# left_revision3_0.net
KiCad netlist of a schematic drawn in EAGLE
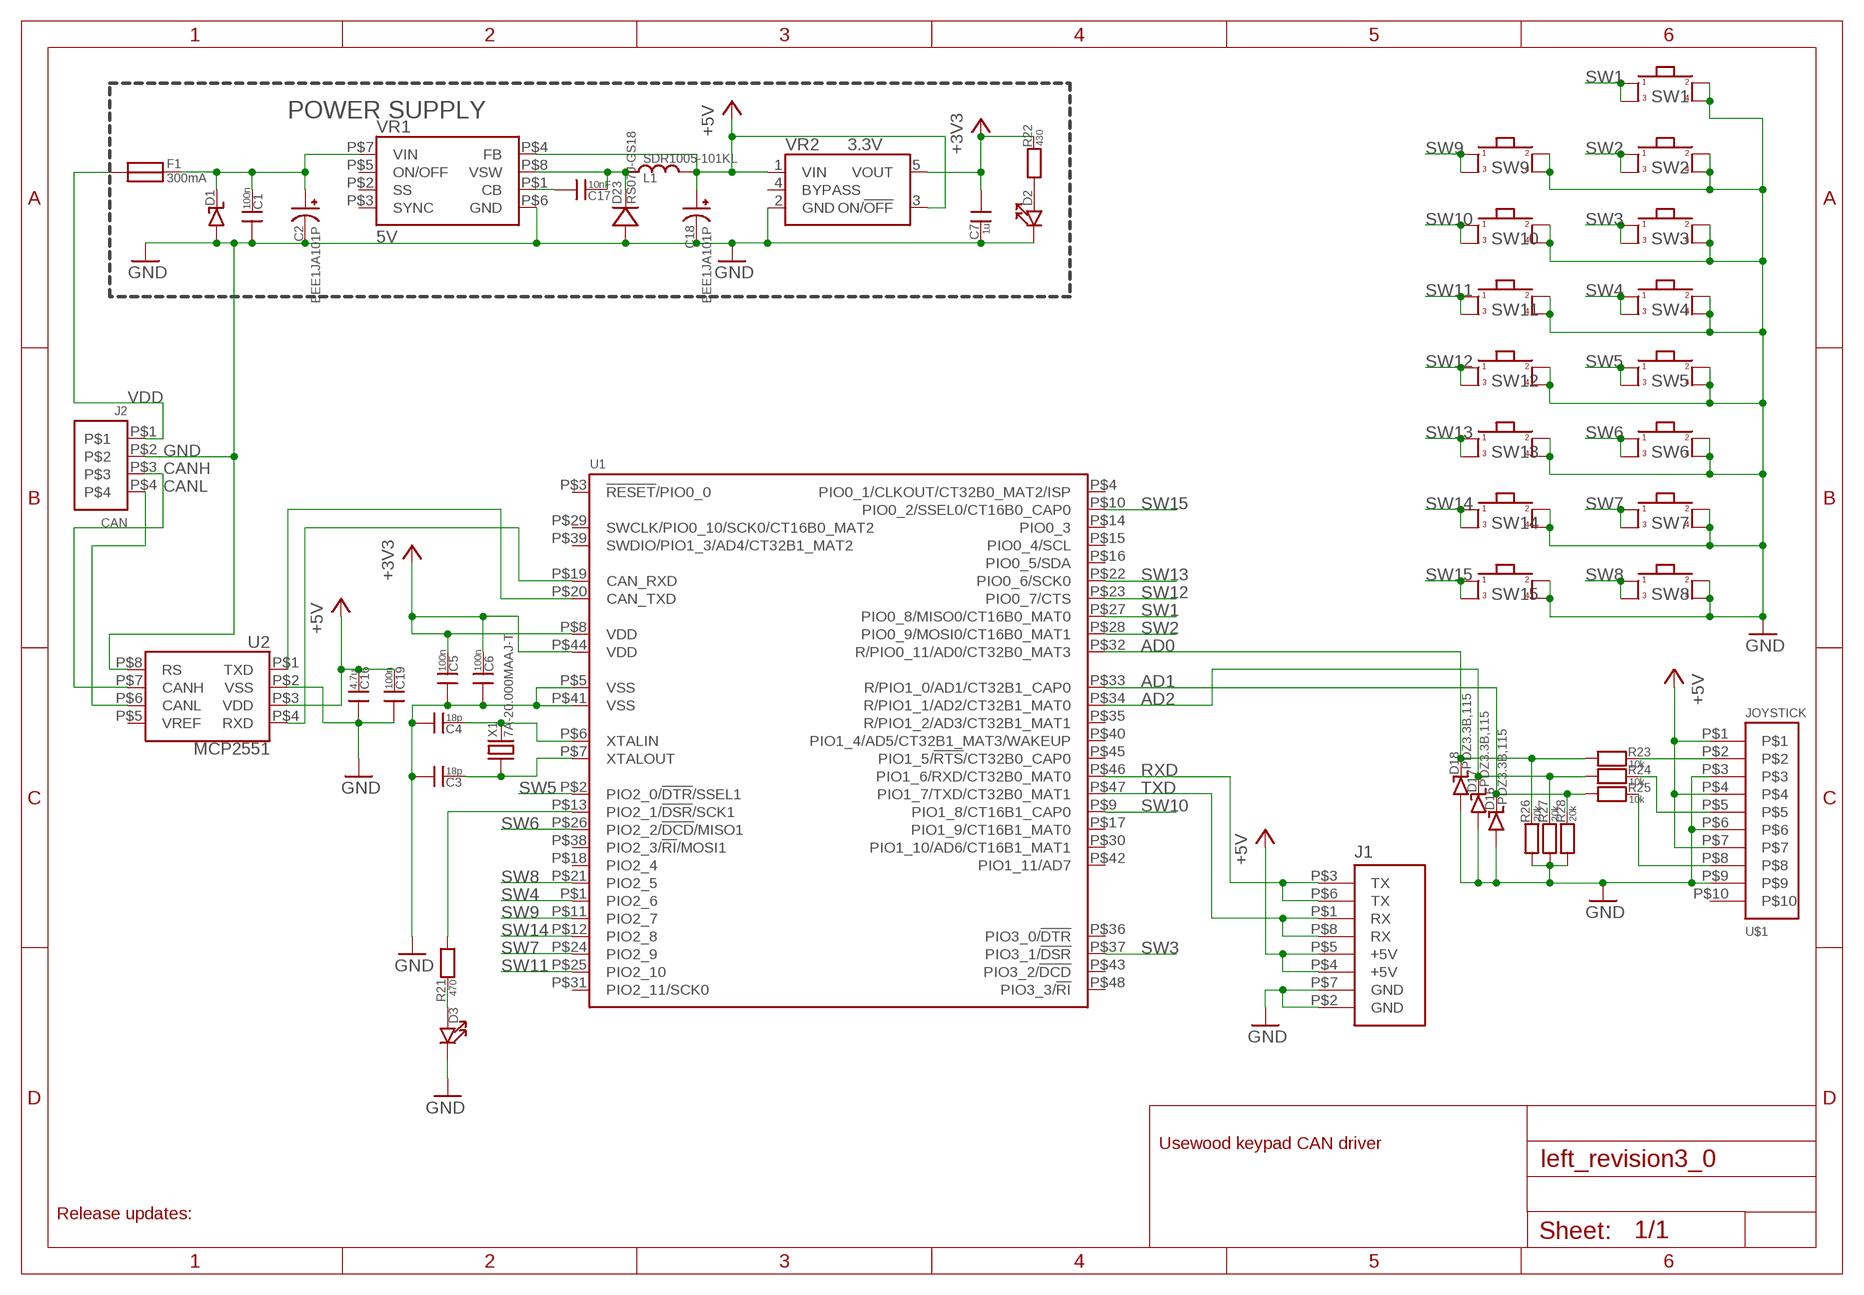
[diagram p0: schematic, sheet 1]

(export (version "E")
  (design (tool "Eeschema 10.0.6"))
  (components
    (comp (ref "C1")
      (value "100n")
      (footprint "eagle-import:0603_SILKSCREEN")
      (libsource (lib "eagle-import") (part "CAP_0603"))
    )
    (comp (ref "C2")
      (value "EEE1JA101P")
      (footprint "eagle-import:CAP_POL_SMD_10X10X10MM")
      (libsource (lib "eagle-import") (part "CAP_POLSMD_10X10X10MM"))
    )
    (comp (ref "C3")
      (value "18p")
      (footprint "eagle-import:0603_SILKSCREEN")
      (libsource (lib "eagle-import") (part "CAP_0603"))
    )
    (comp (ref "C4")
      (value "18p")
      (footprint "eagle-import:0603_SILKSCREEN")
      (libsource (lib "eagle-import") (part "CAP_0603"))
    )
    (comp (ref "C5")
      (value "100n")
      (footprint "eagle-import:0603_SILKSCREEN")
      (libsource (lib "eagle-import") (part "CAP_0603"))
    )
    (comp (ref "C6")
      (value "100n")
      (footprint "eagle-import:0603_SILKSCREEN")
      (libsource (lib "eagle-import") (part "CAP_0603"))
    )
    (comp (ref "C7")
      (value "1u")
      (footprint "eagle-import:0603_SILKSCREEN")
      (libsource (lib "eagle-import") (part "CAP_0603"))
    )
    (comp (ref "C16")
      (value "4.7u")
      (footprint "eagle-import:0603_SILKSCREEN")
      (libsource (lib "eagle-import") (part "CAP_0603"))
    )
    (comp (ref "C17")
      (value "10nF")
      (footprint "eagle-import:0603_SILKSCREEN")
      (libsource (lib "eagle-import") (part "CAP_0603"))
    )
    (comp (ref "C18")
      (value "EEE1JA101P")
      (footprint "eagle-import:CAP_POL_SMD_10X10X10MM")
      (libsource (lib "eagle-import") (part "CAP_POLSMD_10X10X10MM"))
    )
    (comp (ref "C19")
      (value "100n")
      (footprint "eagle-import:0603_SILKSCREEN")
      (libsource (lib "eagle-import") (part "CAP_0603"))
    )
    (comp (ref "D1")
      (value "DIODE_TVSDO-214AA")
      (footprint "eagle-import:DO-214AB")
      (libsource (lib "eagle-import") (part "DIODE_TVSDO-214AA"))
    )
    (comp (ref "D2")
      (value "LED_0603")
      (footprint "eagle-import:0603_SILKSCREEN")
      (libsource (lib "eagle-import") (part "LED_0603"))
    )
    (comp (ref "D3")
      (value "LED_0603")
      (footprint "eagle-import:0603_SILKSCREEN")
      (libsource (lib "eagle-import") (part "LED_0603"))
    )
    (comp (ref "D16")
      (value "PDZ3.3B,115")
      (footprint "eagle-import:SOD123")
      (libsource (lib "eagle-import") (part "DIODE_ZENERSDO123"))
    )
    (comp (ref "D17")
      (value "PDZ3.3B,115")
      (footprint "eagle-import:SOD123")
      (libsource (lib "eagle-import") (part "DIODE_ZENERSDO123"))
    )
    (comp (ref "D18")
      (value "PDZ3.3B,115")
      (footprint "eagle-import:SOD123")
      (libsource (lib "eagle-import") (part "DIODE_ZENERSDO123"))
    )
    (comp (ref "D23")
      (value "RS07J-GS18")
      (footprint "eagle-import:DO219AB")
      (libsource (lib "eagle-import") (part "DIODEDO219AB"))
    )
    (comp (ref "F1")
      (value "300mA")
      (footprint "eagle-import:FUSE_100MA")
      (libsource (lib "eagle-import") (part "FUSE_MC36204_100MA"))
    )
    (comp (ref "J1")
      (value "HEADER_USART_2_SMD")
      (footprint "eagle-import:HEADER_4_2_SMD")
      (libsource (lib "eagle-import") (part "HEADER_USART_2_SMD"))
    )
    (comp (ref "J2")
      (value "CAN")
      (footprint "eagle-import:MOLEX_MICRO_FIT_4WAY_SMD")
      (libsource (lib "eagle-import") (part "MOLEX_MICRO-FIT_4WAY_SMD"))
    )
    (comp (ref "L1")
      (value "SDR1005-101KL")
      (footprint "eagle-import:INDUCTOR_BOURNS_10X13X5MM")
      (libsource (lib "eagle-import") (part "INDUCTORBOURNS_10X13X5MM"))
    )
    (comp (ref "R21")
      (value "470")
      (footprint "eagle-import:0603_SILKSCREEN")
      (libsource (lib "eagle-import") (part "RES_0603"))
    )
    (comp (ref "R22")
      (value "430")
      (footprint "eagle-import:0603_SILKSCREEN")
      (libsource (lib "eagle-import") (part "RES_0603"))
    )
    (comp (ref "R23")
      (value "10k")
      (footprint "eagle-import:0603_SILKSCREEN")
      (libsource (lib "eagle-import") (part "RES_0603"))
    )
    (comp (ref "R24")
      (value "10k")
      (footprint "eagle-import:0603_SILKSCREEN")
      (libsource (lib "eagle-import") (part "RES_0603"))
    )
    (comp (ref "R25")
      (value "10k")
      (footprint "eagle-import:0603_SILKSCREEN")
      (libsource (lib "eagle-import") (part "RES_0603"))
    )
    (comp (ref "R26")
      (value "20k")
      (footprint "eagle-import:0603_SILKSCREEN")
      (libsource (lib "eagle-import") (part "RES_0603"))
    )
    (comp (ref "R27")
      (value "20k")
      (footprint "eagle-import:0603_SILKSCREEN")
      (libsource (lib "eagle-import") (part "RES_0603"))
    )
    (comp (ref "R28")
      (value "20k")
      (footprint "eagle-import:0603_SILKSCREEN")
      (libsource (lib "eagle-import") (part "RES_0603"))
    )
    (comp (ref "SW1")
      (value "SWITCH_EVQP6L")
      (footprint "eagle-import:SWITCH_EVQ9P6B40")
      (libsource (lib "eagle-import") (part "SWITCH_EVQP6L"))
    )
    (comp (ref "SW2")
      (value "SWITCH_EVQP6L")
      (footprint "eagle-import:SWITCH_EVQ9P6B40")
      (libsource (lib "eagle-import") (part "SWITCH_EVQP6L"))
    )
    (comp (ref "SW3")
      (value "SWITCH_EVQP6L")
      (footprint "eagle-import:SWITCH_EVQ9P6B40")
      (libsource (lib "eagle-import") (part "SWITCH_EVQP6L"))
    )
    (comp (ref "SW4")
      (value "SWITCH_EVQP6L")
      (footprint "eagle-import:SWITCH_EVQ9P6B40")
      (libsource (lib "eagle-import") (part "SWITCH_EVQP6L"))
    )
    (comp (ref "SW5")
      (value "SWITCH_EVQP6L")
      (footprint "eagle-import:SWITCH_EVQ9P6B40")
      (libsource (lib "eagle-import") (part "SWITCH_EVQP6L"))
    )
    (comp (ref "SW6")
      (value "SWITCH_EVQP6L")
      (footprint "eagle-import:SWITCH_EVQ9P6B40")
      (libsource (lib "eagle-import") (part "SWITCH_EVQP6L"))
    )
    (comp (ref "SW7")
      (value "SWITCH_EVQP6L")
      (footprint "eagle-import:SWITCH_EVQ9P6B40")
      (libsource (lib "eagle-import") (part "SWITCH_EVQP6L"))
    )
    (comp (ref "SW8")
      (value "SWITCH_EVQP6L")
      (footprint "eagle-import:SWITCH_EVQ9P6B40")
      (libsource (lib "eagle-import") (part "SWITCH_EVQP6L"))
    )
    (comp (ref "SW9")
      (value "SWITCH_EVQP6L")
      (footprint "eagle-import:SWITCH_EVQ9P6B40")
      (libsource (lib "eagle-import") (part "SWITCH_EVQP6L"))
    )
    (comp (ref "SW10")
      (value "SWITCH_EVQP6L")
      (footprint "eagle-import:SWITCH_EVQ9P6B40")
      (libsource (lib "eagle-import") (part "SWITCH_EVQP6L"))
    )
    (comp (ref "SW11")
      (value "SWITCH_EVQP6L")
      (footprint "eagle-import:SWITCH_EVQ9P6B40")
      (libsource (lib "eagle-import") (part "SWITCH_EVQP6L"))
    )
    (comp (ref "SW12")
      (value "SWITCH_EVQP6L")
      (footprint "eagle-import:SWITCH_EVQ9P6B40")
      (libsource (lib "eagle-import") (part "SWITCH_EVQP6L"))
    )
    (comp (ref "SW13")
      (value "SWITCH_EVQP6L")
      (footprint "eagle-import:SWITCH_EVQ9P6B40")
      (libsource (lib "eagle-import") (part "SWITCH_EVQP6L"))
    )
    (comp (ref "SW14")
      (value "SWITCH_EVQP6L")
      (footprint "eagle-import:SWITCH_EVQ9P6B40")
      (libsource (lib "eagle-import") (part "SWITCH_EVQP6L"))
    )
    (comp (ref "SW15")
      (value "SWITCH_EVQP6L")
      (footprint "eagle-import:SWITCH_EVQ9P6B40")
      (libsource (lib "eagle-import") (part "SWITCH_EVQP6L"))
    )
    (comp (ref "U$1")
      (value "JOYSTICK")
      (footprint "eagle-import:MOLEX_MICRO_FIT_10WAY_SMD")
      (libsource (lib "eagle-import") (part "MOLEX_MICRO-FIT_10WAY_SMD"))
    )
    (comp (ref "U1")
      (value "LPC11C14_QFP48")
      (footprint "eagle-import:QFP48")
      (libsource (lib "eagle-import") (part "LPC11C14_QFP48"))
    )
    (comp (ref "U2")
      (value "MCP2551")
      (footprint "eagle-import:SOIC8")
      (libsource (lib "eagle-import") (part "MCP2551_SOIC8"))
    )
    (comp (ref "VR1")
      (value "5V")
      (footprint "eagle-import:SOIC8")
      (libsource (lib "eagle-import") (part "LM2671SOIC8"))
    )
    (comp (ref "VR2")
      (value "3.3V")
      (footprint "eagle-import:SOP5")
      (libsource (lib "eagle-import") (part "REG_LP2985_SOP5"))
    )
    (comp (ref "X1")
      (value "7A-20.000MAAJ-T")
      (footprint "eagle-import:XTAL_SMD_5X3.2")
      (libsource (lib "eagle-import") (part "XTAL_7A-12.000MAAJ-T"))
    )
  )
  (nets
    (net (code "1") (name "+3V3") (class "Default")
      (node (ref "C5") (pin "1") (pinfunction "P$2_1") (pintype "bidirectional"))
      (node (ref "C6") (pin "1") (pinfunction "P$2_1") (pintype "bidirectional"))
      (node (ref "C7") (pin "0") (pinfunction "P$1_0") (pintype "bidirectional"))
      (node (ref "R22") (pin "1") (pinfunction "P$2_1") (pintype "bidirectional"))
      (node (ref "U1") (pin "P$44") (pinfunction "VDD_P$44") (pintype "bidirectional"))
      (node (ref "U1") (pin "P$8") (pinfunction "VDD_P$8") (pintype "bidirectional"))
      (node (ref "VR2") (pin "5") (pinfunction "VOUT_5") (pintype "bidirectional"))
    )
    (net (code "2") (name "+5V") (class "Default")
      (node (ref "C16") (pin "1") (pinfunction "P$2_1") (pintype "bidirectional"))
      (node (ref "C18") (pin "+") (pinfunction "+_+") (pintype "bidirectional"))
      (node (ref "C19") (pin "1") (pinfunction "P$2_1") (pintype "bidirectional"))
      (node (ref "J1") (pin "P$4") (pinfunction "+5V_P$4") (pintype "bidirectional"))
      (node (ref "J1") (pin "P$5") (pinfunction "+5V_P$5") (pintype "bidirectional"))
      (node (ref "L1") (pin "P$2") (pinfunction "P$2_P$2") (pintype "bidirectional"))
      (node (ref "U$1") (pin "P$1") (pinfunction "P$1_P$1") (pintype "bidirectional"))
      (node (ref "U$1") (pin "P$4") (pinfunction "P$4_P$4") (pintype "bidirectional"))
      (node (ref "U$1") (pin "P$7") (pinfunction "P$7_P$7") (pintype "bidirectional"))
      (node (ref "U2") (pin "P$3") (pinfunction "VDD_P$3") (pintype "bidirectional"))
      (node (ref "VR1") (pin "P$4") (pinfunction "FB_P$4") (pintype "bidirectional"))
      (node (ref "VR2") (pin "1") (pinfunction "VIN_1") (pintype "bidirectional"))
      (node (ref "VR2") (pin "3") (pinfunction "ON/~{OFF}_3") (pintype "bidirectional"))
    )
    (net (code "3") (name "/AD0") (class "Default")
      (node (ref "D18") (pin "P$2") (pinfunction "N_P$2") (pintype "bidirectional"))
      (node (ref "R23") (pin "0") (pinfunction "P$1_0") (pintype "bidirectional"))
      (node (ref "R26") (pin "1") (pinfunction "P$2_1") (pintype "bidirectional"))
      (node (ref "U1") (pin "P$32") (pinfunction "R/PIO0_11/AD0/CT32B0_MAT3_P$32") (pintype "bidirectional"))
    )
    (net (code "4") (name "/AD1") (class "Default")
      (node (ref "D16") (pin "P$2") (pinfunction "N_P$2") (pintype "bidirectional"))
      (node (ref "R25") (pin "0") (pinfunction "P$1_0") (pintype "bidirectional"))
      (node (ref "R28") (pin "1") (pinfunction "P$2_1") (pintype "bidirectional"))
      (node (ref "U1") (pin "P$33") (pinfunction "R/PIO1_0/AD1/CT32B1_CAP0_P$33") (pintype "bidirectional"))
    )
    (net (code "5") (name "/AD2") (class "Default")
      (node (ref "D17") (pin "P$2") (pinfunction "N_P$2") (pintype "bidirectional"))
      (node (ref "R24") (pin "0") (pinfunction "P$1_0") (pintype "bidirectional"))
      (node (ref "R27") (pin "1") (pinfunction "P$2_1") (pintype "bidirectional"))
      (node (ref "U1") (pin "P$34") (pinfunction "R/PIO1_1/AD2/CT32B1_MAT0_P$34") (pintype "bidirectional"))
    )
    (net (code "6") (name "/CANH") (class "Default")
      (node (ref "J2") (pin "P$3") (pinfunction "P$3_P$3") (pintype "bidirectional"))
      (node (ref "U2") (pin "P$7") (pinfunction "CANH_P$7") (pintype "bidirectional"))
    )
    (net (code "7") (name "/CANL") (class "Default")
      (node (ref "J2") (pin "P$4") (pinfunction "P$4_P$4") (pintype "bidirectional"))
      (node (ref "U2") (pin "P$6") (pinfunction "CANL_P$6") (pintype "bidirectional"))
    )
    (net (code "8") (name "/RXD") (class "Default")
      (node (ref "J1") (pin "P$3") (pinfunction "TX_P$3") (pintype "bidirectional"))
      (node (ref "J1") (pin "P$6") (pinfunction "TX_P$6") (pintype "bidirectional"))
      (node (ref "U1") (pin "P$46") (pinfunction "PIO1_6/RXD/CT32B0_MAT0_P$46") (pintype "bidirectional"))
    )
    (net (code "9") (name "/SW1") (class "Default")
      (node (ref "SW1") (pin "A") (pinfunction "P$1_A") (pintype "bidirectional"))
      (node (ref "SW1") (pin "A'") (pinfunction "P$3_A'") (pintype "bidirectional"))
      (node (ref "U1") (pin "P$27") (pinfunction "PIO0_8/MISO0/CT16B0_MAT0_P$27") (pintype "bidirectional"))
    )
    (net (code "10") (name "/SW2") (class "Default")
      (node (ref "SW2") (pin "A") (pinfunction "P$1_A") (pintype "bidirectional"))
      (node (ref "SW2") (pin "A'") (pinfunction "P$3_A'") (pintype "bidirectional"))
      (node (ref "U1") (pin "P$28") (pinfunction "PIO0_9/MOSI0/CT16B0_MAT1_P$28") (pintype "bidirectional"))
    )
    (net (code "11") (name "/SW3") (class "Default")
      (node (ref "SW3") (pin "A") (pinfunction "P$1_A") (pintype "bidirectional"))
      (node (ref "SW3") (pin "A'") (pinfunction "P$3_A'") (pintype "bidirectional"))
      (node (ref "U1") (pin "P$37") (pinfunction "PIO3_1/~{DSR}_P$37") (pintype "bidirectional"))
    )
    (net (code "12") (name "/SW4") (class "Default")
      (node (ref "SW4") (pin "A") (pinfunction "P$1_A") (pintype "bidirectional"))
      (node (ref "SW4") (pin "A'") (pinfunction "P$3_A'") (pintype "bidirectional"))
      (node (ref "U1") (pin "P$1") (pinfunction "PIO2_6_P$1") (pintype "bidirectional"))
    )
    (net (code "13") (name "/SW5") (class "Default")
      (node (ref "SW5") (pin "A") (pinfunction "P$1_A") (pintype "bidirectional"))
      (node (ref "SW5") (pin "A'") (pinfunction "P$3_A'") (pintype "bidirectional"))
      (node (ref "U1") (pin "P$2") (pinfunction "PIO2_0/~{DTR}/SSEL1_P$2") (pintype "bidirectional"))
    )
    (net (code "14") (name "/SW6") (class "Default")
      (node (ref "SW6") (pin "A") (pinfunction "P$1_A") (pintype "bidirectional"))
      (node (ref "SW6") (pin "A'") (pinfunction "P$3_A'") (pintype "bidirectional"))
      (node (ref "U1") (pin "P$26") (pinfunction "PIO2_2/~{DCD}/MISO1_P$26") (pintype "bidirectional"))
    )
    (net (code "15") (name "/SW7") (class "Default")
      (node (ref "SW7") (pin "A") (pinfunction "P$1_A") (pintype "bidirectional"))
      (node (ref "SW7") (pin "A'") (pinfunction "P$3_A'") (pintype "bidirectional"))
      (node (ref "U1") (pin "P$24") (pinfunction "PIO2_9_P$24") (pintype "bidirectional"))
    )
    (net (code "16") (name "/SW8") (class "Default")
      (node (ref "SW8") (pin "A") (pinfunction "P$1_A") (pintype "bidirectional"))
      (node (ref "SW8") (pin "A'") (pinfunction "P$3_A'") (pintype "bidirectional"))
      (node (ref "U1") (pin "P$21") (pinfunction "PIO2_5_P$21") (pintype "bidirectional"))
    )
    (net (code "17") (name "/SW9") (class "Default")
      (node (ref "SW9") (pin "A") (pinfunction "P$1_A") (pintype "bidirectional"))
      (node (ref "SW9") (pin "A'") (pinfunction "P$3_A'") (pintype "bidirectional"))
      (node (ref "U1") (pin "P$11") (pinfunction "PIO2_7_P$11") (pintype "bidirectional"))
    )
    (net (code "18") (name "/SW10") (class "Default")
      (node (ref "SW10") (pin "A") (pinfunction "P$1_A") (pintype "bidirectional"))
      (node (ref "SW10") (pin "A'") (pinfunction "P$3_A'") (pintype "bidirectional"))
      (node (ref "U1") (pin "P$9") (pinfunction "PIO1_8/CT16B1_CAP0_P$9") (pintype "bidirectional"))
    )
    (net (code "19") (name "/SW11") (class "Default")
      (node (ref "SW11") (pin "A") (pinfunction "P$1_A") (pintype "bidirectional"))
      (node (ref "SW11") (pin "A'") (pinfunction "P$3_A'") (pintype "bidirectional"))
      (node (ref "U1") (pin "P$25") (pinfunction "PIO2_10_P$25") (pintype "bidirectional"))
    )
    (net (code "20") (name "/SW12") (class "Default")
      (node (ref "SW12") (pin "A") (pinfunction "P$1_A") (pintype "bidirectional"))
      (node (ref "SW12") (pin "A'") (pinfunction "P$3_A'") (pintype "bidirectional"))
      (node (ref "U1") (pin "P$23") (pinfunction "PIO0_7/CTS_P$23") (pintype "bidirectional"))
    )
    (net (code "21") (name "/SW13") (class "Default")
      (node (ref "SW13") (pin "A") (pinfunction "P$1_A") (pintype "bidirectional"))
      (node (ref "SW13") (pin "A'") (pinfunction "P$3_A'") (pintype "bidirectional"))
      (node (ref "U1") (pin "P$22") (pinfunction "PIO0_6/SCK0_P$22") (pintype "bidirectional"))
    )
    (net (code "22") (name "/SW14") (class "Default")
      (node (ref "SW14") (pin "A") (pinfunction "P$1_A") (pintype "bidirectional"))
      (node (ref "SW14") (pin "A'") (pinfunction "P$3_A'") (pintype "bidirectional"))
      (node (ref "U1") (pin "P$12") (pinfunction "PIO2_8_P$12") (pintype "bidirectional"))
    )
    (net (code "23") (name "/SW15") (class "Default")
      (node (ref "SW15") (pin "A") (pinfunction "P$1_A") (pintype "bidirectional"))
      (node (ref "SW15") (pin "A'") (pinfunction "P$3_A'") (pintype "bidirectional"))
      (node (ref "U1") (pin "P$10") (pinfunction "PIO0_2/SSEL0/CT16B0_CAP0_P$10") (pintype "bidirectional"))
    )
    (net (code "24") (name "/TXD") (class "Default")
      (node (ref "J1") (pin "P$1") (pinfunction "RX_P$1") (pintype "bidirectional"))
      (node (ref "J1") (pin "P$8") (pinfunction "RX_P$8") (pintype "bidirectional"))
      (node (ref "U1") (pin "P$47") (pinfunction "PIO1_7/TXD/CT32B0_MAT1_P$47") (pintype "bidirectional"))
    )
    (net (code "25") (name "/VDD") (class "Default")
      (node (ref "F1") (pin "P$1") (pinfunction "P$1_P$1") (pintype "bidirectional"))
      (node (ref "J2") (pin "P$1") (pinfunction "P$1_P$1") (pintype "bidirectional"))
    )
    (net (code "26") (name "GND") (class "Default")
      (node (ref "C1") (pin "0") (pinfunction "P$1_0") (pintype "bidirectional"))
      (node (ref "C16") (pin "0") (pinfunction "P$1_0") (pintype "bidirectional"))
      (node (ref "C18") (pin "-") (pinfunction "-_-") (pintype "bidirectional"))
      (node (ref "C19") (pin "0") (pinfunction "P$1_0") (pintype "bidirectional"))
      (node (ref "C2") (pin "-") (pinfunction "-_-") (pintype "bidirectional"))
      (node (ref "C3") (pin "0") (pinfunction "P$1_0") (pintype "bidirectional"))
      (node (ref "C4") (pin "0") (pinfunction "P$1_0") (pintype "bidirectional"))
      (node (ref "C5") (pin "0") (pinfunction "P$1_0") (pintype "bidirectional"))
      (node (ref "C6") (pin "0") (pinfunction "P$1_0") (pintype "bidirectional"))
      (node (ref "C7") (pin "1") (pinfunction "P$2_1") (pintype "bidirectional"))
      (node (ref "D1") (pin "P$1") (pinfunction "P_P$1") (pintype "bidirectional"))
      (node (ref "D16") (pin "P$1") (pinfunction "P_P$1") (pintype "bidirectional"))
      (node (ref "D17") (pin "P$1") (pinfunction "P_P$1") (pintype "bidirectional"))
      (node (ref "D18") (pin "P$1") (pinfunction "P_P$1") (pintype "bidirectional"))
      (node (ref "D2") (pin "1") (pinfunction "1_1") (pintype "bidirectional"))
      (node (ref "D23") (pin "P$1") (pinfunction "P_P$1") (pintype "bidirectional"))
      (node (ref "D3") (pin "1") (pinfunction "1_1") (pintype "bidirectional"))
      (node (ref "J1") (pin "P$2") (pinfunction "GND_P$2") (pintype "bidirectional"))
      (node (ref "J1") (pin "P$7") (pinfunction "GND_P$7") (pintype "bidirectional"))
      (node (ref "J2") (pin "P$2") (pinfunction "P$2_P$2") (pintype "bidirectional"))
      (node (ref "R26") (pin "0") (pinfunction "P$1_0") (pintype "bidirectional"))
      (node (ref "R27") (pin "0") (pinfunction "P$1_0") (pintype "bidirectional"))
      (node (ref "R28") (pin "0") (pinfunction "P$1_0") (pintype "bidirectional"))
      (node (ref "SW1") (pin "B") (pinfunction "P$2_B") (pintype "bidirectional"))
      (node (ref "SW1") (pin "B'") (pinfunction "P$4_B'") (pintype "bidirectional"))
      (node (ref "SW10") (pin "B") (pinfunction "P$2_B") (pintype "bidirectional"))
      (node (ref "SW10") (pin "B'") (pinfunction "P$4_B'") (pintype "bidirectional"))
      (node (ref "SW11") (pin "B") (pinfunction "P$2_B") (pintype "bidirectional"))
      (node (ref "SW11") (pin "B'") (pinfunction "P$4_B'") (pintype "bidirectional"))
      (node (ref "SW12") (pin "B") (pinfunction "P$2_B") (pintype "bidirectional"))
      (node (ref "SW12") (pin "B'") (pinfunction "P$4_B'") (pintype "bidirectional"))
      (node (ref "SW13") (pin "B") (pinfunction "P$2_B") (pintype "bidirectional"))
      (node (ref "SW13") (pin "B'") (pinfunction "P$4_B'") (pintype "bidirectional"))
      (node (ref "SW14") (pin "B") (pinfunction "P$2_B") (pintype "bidirectional"))
      (node (ref "SW14") (pin "B'") (pinfunction "P$4_B'") (pintype "bidirectional"))
      (node (ref "SW15") (pin "B") (pinfunction "P$2_B") (pintype "bidirectional"))
      (node (ref "SW15") (pin "B'") (pinfunction "P$4_B'") (pintype "bidirectional"))
      (node (ref "SW2") (pin "B") (pinfunction "P$2_B") (pintype "bidirectional"))
      (node (ref "SW2") (pin "B'") (pinfunction "P$4_B'") (pintype "bidirectional"))
      (node (ref "SW3") (pin "B") (pinfunction "P$2_B") (pintype "bidirectional"))
      (node (ref "SW3") (pin "B'") (pinfunction "P$4_B'") (pintype "bidirectional"))
      (node (ref "SW4") (pin "B") (pinfunction "P$2_B") (pintype "bidirectional"))
      (node (ref "SW4") (pin "B'") (pinfunction "P$4_B'") (pintype "bidirectional"))
      (node (ref "SW5") (pin "B") (pinfunction "P$2_B") (pintype "bidirectional"))
      (node (ref "SW5") (pin "B'") (pinfunction "P$4_B'") (pintype "bidirectional"))
      (node (ref "SW6") (pin "B") (pinfunction "P$2_B") (pintype "bidirectional"))
      (node (ref "SW6") (pin "B'") (pinfunction "P$4_B'") (pintype "bidirectional"))
      (node (ref "SW7") (pin "B") (pinfunction "P$2_B") (pintype "bidirectional"))
      (node (ref "SW7") (pin "B'") (pinfunction "P$4_B'") (pintype "bidirectional"))
      (node (ref "SW8") (pin "B") (pinfunction "P$2_B") (pintype "bidirectional"))
      (node (ref "SW8") (pin "B'") (pinfunction "P$4_B'") (pintype "bidirectional"))
      (node (ref "SW9") (pin "B") (pinfunction "P$2_B") (pintype "bidirectional"))
      (node (ref "SW9") (pin "B'") (pinfunction "P$4_B'") (pintype "bidirectional"))
      (node (ref "U$1") (pin "P$3") (pinfunction "P$3_P$3") (pintype "bidirectional"))
      (node (ref "U$1") (pin "P$6") (pinfunction "P$6_P$6") (pintype "bidirectional"))
      (node (ref "U$1") (pin "P$9") (pinfunction "P$9_P$9") (pintype "bidirectional"))
      (node (ref "U1") (pin "P$41") (pinfunction "VSS_P$41") (pintype "bidirectional"))
      (node (ref "U1") (pin "P$5") (pinfunction "VSS_P$5") (pintype "bidirectional"))
      (node (ref "U2") (pin "P$2") (pinfunction "VSS_P$2") (pintype "bidirectional"))
      (node (ref "U2") (pin "P$8") (pinfunction "RS_P$8") (pintype "bidirectional"))
      (node (ref "VR1") (pin "P$6") (pinfunction "GND_P$6") (pintype "bidirectional"))
      (node (ref "VR2") (pin "2") (pinfunction "GND_2") (pintype "bidirectional"))
    )
    (net (code "27") (name "Net-(C1-P$2)") (class "Default")
      (node (ref "C1") (pin "1") (pinfunction "P$2_1") (pintype "bidirectional"))
      (node (ref "C2") (pin "+") (pinfunction "+_+") (pintype "bidirectional"))
      (node (ref "D1") (pin "P$2") (pinfunction "N_P$2") (pintype "bidirectional"))
      (node (ref "F1") (pin "P$2") (pinfunction "P$2_P$2") (pintype "bidirectional"))
      (node (ref "VR1") (pin "P$7") (pinfunction "VIN_P$7") (pintype "bidirectional"))
    )
    (net (code "28") (name "Net-(C3-P$2)") (class "Default")
      (node (ref "C3") (pin "1") (pinfunction "P$2_1") (pintype "bidirectional"))
      (node (ref "U1") (pin "P$7") (pinfunction "XTALOUT_P$7") (pintype "bidirectional"))
      (node (ref "X1") (pin "P$1") (pinfunction "P$1_P$1") (pintype "bidirectional"))
    )
    (net (code "29") (name "Net-(C4-P$2)") (class "Default")
      (node (ref "C4") (pin "1") (pinfunction "P$2_1") (pintype "bidirectional"))
      (node (ref "U1") (pin "P$6") (pinfunction "XTALIN_P$6") (pintype "bidirectional"))
      (node (ref "X1") (pin "P$2") (pinfunction "P$2_P$2") (pintype "bidirectional"))
    )
    (net (code "30") (name "Net-(C17-P$1)") (class "Default")
      (node (ref "C17") (pin "0") (pinfunction "P$1_0") (pintype "bidirectional"))
      (node (ref "VR1") (pin "P$1") (pinfunction "CB_P$1") (pintype "bidirectional"))
    )
    (net (code "31") (name "Net-(C17-P$2)") (class "Default")
      (node (ref "C17") (pin "1") (pinfunction "P$2_1") (pintype "bidirectional"))
      (node (ref "D23") (pin "P$2") (pinfunction "N_P$2") (pintype "bidirectional"))
      (node (ref "L1") (pin "P$1") (pinfunction "P$1_P$1") (pintype "bidirectional"))
      (node (ref "VR1") (pin "P$8") (pinfunction "VSW_P$8") (pintype "bidirectional"))
    )
    (net (code "32") (name "Net-(R21-P$1)") (class "Default")
      (node (ref "R21") (pin "0") (pinfunction "P$1_0") (pintype "bidirectional"))
      (node (ref "U1") (pin "P$13") (pinfunction "PIO2_1/~{DSR}/SCK1_P$13") (pintype "bidirectional"))
    )
    (net (code "33") (name "Net-(R21-P$2)") (class "Default")
      (node (ref "D3") (pin "0") (pinfunction "0_0") (pintype "bidirectional"))
      (node (ref "R21") (pin "1") (pinfunction "P$2_1") (pintype "bidirectional"))
    )
    (net (code "34") (name "Net-(R22-P$1)") (class "Default")
      (node (ref "D2") (pin "0") (pinfunction "0_0") (pintype "bidirectional"))
      (node (ref "R22") (pin "0") (pinfunction "P$1_0") (pintype "bidirectional"))
    )
    (net (code "35") (name "Net-(R23-P$2)") (class "Default")
      (node (ref "R23") (pin "1") (pinfunction "P$2_1") (pintype "bidirectional"))
      (node (ref "U$1") (pin "P$2") (pinfunction "P$2_P$2") (pintype "bidirectional"))
    )
    (net (code "36") (name "Net-(R24-P$2)") (class "Default")
      (node (ref "R24") (pin "1") (pinfunction "P$2_1") (pintype "bidirectional"))
      (node (ref "U$1") (pin "P$5") (pinfunction "P$5_P$5") (pintype "bidirectional"))
    )
    (net (code "37") (name "Net-(R25-P$2)") (class "Default")
      (node (ref "R25") (pin "1") (pinfunction "P$2_1") (pintype "bidirectional"))
      (node (ref "U$1") (pin "P$8") (pinfunction "P$8_P$8") (pintype "bidirectional"))
    )
    (net (code "38") (name "Net-(U1-CAN_RXD)") (class "Default")
      (node (ref "U1") (pin "P$19") (pinfunction "CAN_RXD_P$19") (pintype "bidirectional"))
      (node (ref "U2") (pin "P$4") (pinfunction "RXD_P$4") (pintype "bidirectional"))
    )
    (net (code "39") (name "Net-(U1-CAN_TXD)") (class "Default")
      (node (ref "U1") (pin "P$20") (pinfunction "CAN_TXD_P$20") (pintype "bidirectional"))
      (node (ref "U2") (pin "P$1") (pinfunction "TXD_P$1") (pintype "bidirectional"))
    )
    (net (code "40") (name "unconnected-(U$1-PadP$10)") (class "Default")
      (node (ref "U$1") (pin "P$10") (pinfunction "P$10_P$10") (pintype "bidirectional"))
    )
    (net (code "41") (name "unconnected-(U1-PIO0_1{slash}CLKOUT{slash}CT32B0_MAT2{slash}ISP-PadP$4)") (class "Default")
      (node (ref "U1") (pin "P$4") (pinfunction "PIO0_1/CLKOUT/CT32B0_MAT2/ISP_P$4") (pintype "bidirectional"))
    )
    (net (code "42") (name "unconnected-(U1-PIO0_3-PadP$14)") (class "Default")
      (node (ref "U1") (pin "P$14") (pinfunction "PIO0_3_P$14") (pintype "bidirectional"))
    )
    (net (code "43") (name "unconnected-(U1-PIO0_4{slash}SCL-PadP$15)") (class "Default")
      (node (ref "U1") (pin "P$15") (pinfunction "PIO0_4/SCL_P$15") (pintype "bidirectional"))
    )
    (net (code "44") (name "unconnected-(U1-PIO0_5{slash}SDA-PadP$16)") (class "Default")
      (node (ref "U1") (pin "P$16") (pinfunction "PIO0_5/SDA_P$16") (pintype "bidirectional"))
    )
    (net (code "45") (name "unconnected-(U1-PIO1_4{slash}AD5{slash}CT32B1_MAT3{slash}WAKEUP-PadP$40)") (class "Default")
      (node (ref "U1") (pin "P$40") (pinfunction "PIO1_4/AD5/CT32B1_MAT3/WAKEUP_P$40") (pintype "bidirectional"))
    )
    (net (code "46") (name "unconnected-(U1-PIO1_5{slash}~{RTS}{slash}CT32B0_CAP0-PadP$45)") (class "Default")
      (node (ref "U1") (pin "P$45") (pinfunction "PIO1_5/~{RTS}/CT32B0_CAP0_P$45") (pintype "bidirectional"))
    )
    (net (code "47") (name "unconnected-(U1-PIO1_9{slash}CT16B1_MAT0-PadP$17)") (class "Default")
      (node (ref "U1") (pin "P$17") (pinfunction "PIO1_9/CT16B1_MAT0_P$17") (pintype "bidirectional"))
    )
    (net (code "48") (name "unconnected-(U1-PIO1_10{slash}AD6{slash}CT16B1_MAT1-PadP$30)") (class "Default")
      (node (ref "U1") (pin "P$30") (pinfunction "PIO1_10/AD6/CT16B1_MAT1_P$30") (pintype "bidirectional"))
    )
    (net (code "49") (name "unconnected-(U1-PIO1_11{slash}AD7-PadP$42)") (class "Default")
      (node (ref "U1") (pin "P$42") (pinfunction "PIO1_11/AD7_P$42") (pintype "bidirectional"))
    )
    (net (code "50") (name "unconnected-(U1-PIO2_3{slash}~{RI}{slash}MOSI1-PadP$38)") (class "Default")
      (node (ref "U1") (pin "P$38") (pinfunction "PIO2_3/~{RI}/MOSI1_P$38") (pintype "bidirectional"))
    )
    (net (code "51") (name "unconnected-(U1-PIO2_4-PadP$18)") (class "Default")
      (node (ref "U1") (pin "P$18") (pinfunction "PIO2_4_P$18") (pintype "bidirectional"))
    )
    (net (code "52") (name "unconnected-(U1-PIO2_11{slash}SCK0-PadP$31)") (class "Default")
      (node (ref "U1") (pin "P$31") (pinfunction "PIO2_11/SCK0_P$31") (pintype "bidirectional"))
    )
    (net (code "53") (name "unconnected-(U1-PIO3_0{slash}~{DTR}-PadP$36)") (class "Default")
      (node (ref "U1") (pin "P$36") (pinfunction "PIO3_0/~{DTR}_P$36") (pintype "bidirectional"))
    )
    (net (code "54") (name "unconnected-(U1-PIO3_2{slash}~{DCD}-PadP$43)") (class "Default")
      (node (ref "U1") (pin "P$43") (pinfunction "PIO3_2/~{DCD}_P$43") (pintype "bidirectional"))
    )
    (net (code "55") (name "unconnected-(U1-PIO3_3{slash}~{RI}-PadP$48)") (class "Default")
      (node (ref "U1") (pin "P$48") (pinfunction "PIO3_3/~{RI}_P$48") (pintype "bidirectional"))
    )
    (net (code "56") (name "unconnected-(U1-R{slash}PIO1_2{slash}AD3{slash}CT32B1_MAT1-PadP$35)") (class "Default")
      (node (ref "U1") (pin "P$35") (pinfunction "R/PIO1_2/AD3/CT32B1_MAT1_P$35") (pintype "bidirectional"))
    )
    (net (code "57") (name "unconnected-(U1-SWCLK{slash}PIO0_10{slash}SCK0{slash}CT16B0_MAT2-PadP$29)") (class "Default")
      (node (ref "U1") (pin "P$29") (pinfunction "SWCLK/PIO0_10/SCK0/CT16B0_MAT2_P$29") (pintype "bidirectional"))
    )
    (net (code "58") (name "unconnected-(U1-SWDIO{slash}PIO1_3{slash}AD4{slash}CT32B1_MAT2-PadP$39)") (class "Default")
      (node (ref "U1") (pin "P$39") (pinfunction "SWDIO/PIO1_3/AD4/CT32B1_MAT2_P$39") (pintype "bidirectional"))
    )
    (net (code "59") (name "unconnected-(U1-~{RESET}{slash}PIO0_0-PadP$3)") (class "Default")
      (node (ref "U1") (pin "P$3") (pinfunction "~{RESET}/PIO0_0_P$3") (pintype "bidirectional"))
    )
    (net (code "60") (name "unconnected-(U2-VREF-PadP$5)") (class "Default")
      (node (ref "U2") (pin "P$5") (pinfunction "VREF_P$5") (pintype "bidirectional"))
    )
    (net (code "61") (name "unconnected-(VR1-ON{slash}OFF-PadP$5)") (class "Default")
      (node (ref "VR1") (pin "P$5") (pinfunction "ON/OFF_P$5") (pintype "bidirectional"))
    )
    (net (code "62") (name "unconnected-(VR1-SS-PadP$2)") (class "Default")
      (node (ref "VR1") (pin "P$2") (pinfunction "SS_P$2") (pintype "bidirectional"))
    )
    (net (code "63") (name "unconnected-(VR1-SYNC-PadP$3)") (class "Default")
      (node (ref "VR1") (pin "P$3") (pinfunction "SYNC_P$3") (pintype "bidirectional"))
    )
    (net (code "64") (name "unconnected-(VR2-BYPASS-Pad4)") (class "Default")
      (node (ref "VR2") (pin "4") (pinfunction "BYPASS_4") (pintype "bidirectional"))
    )
  )
)
